# SCH_GPS-rx_2026-03-24.net
KiCad netlist of a schematic drawn in EasyEDA
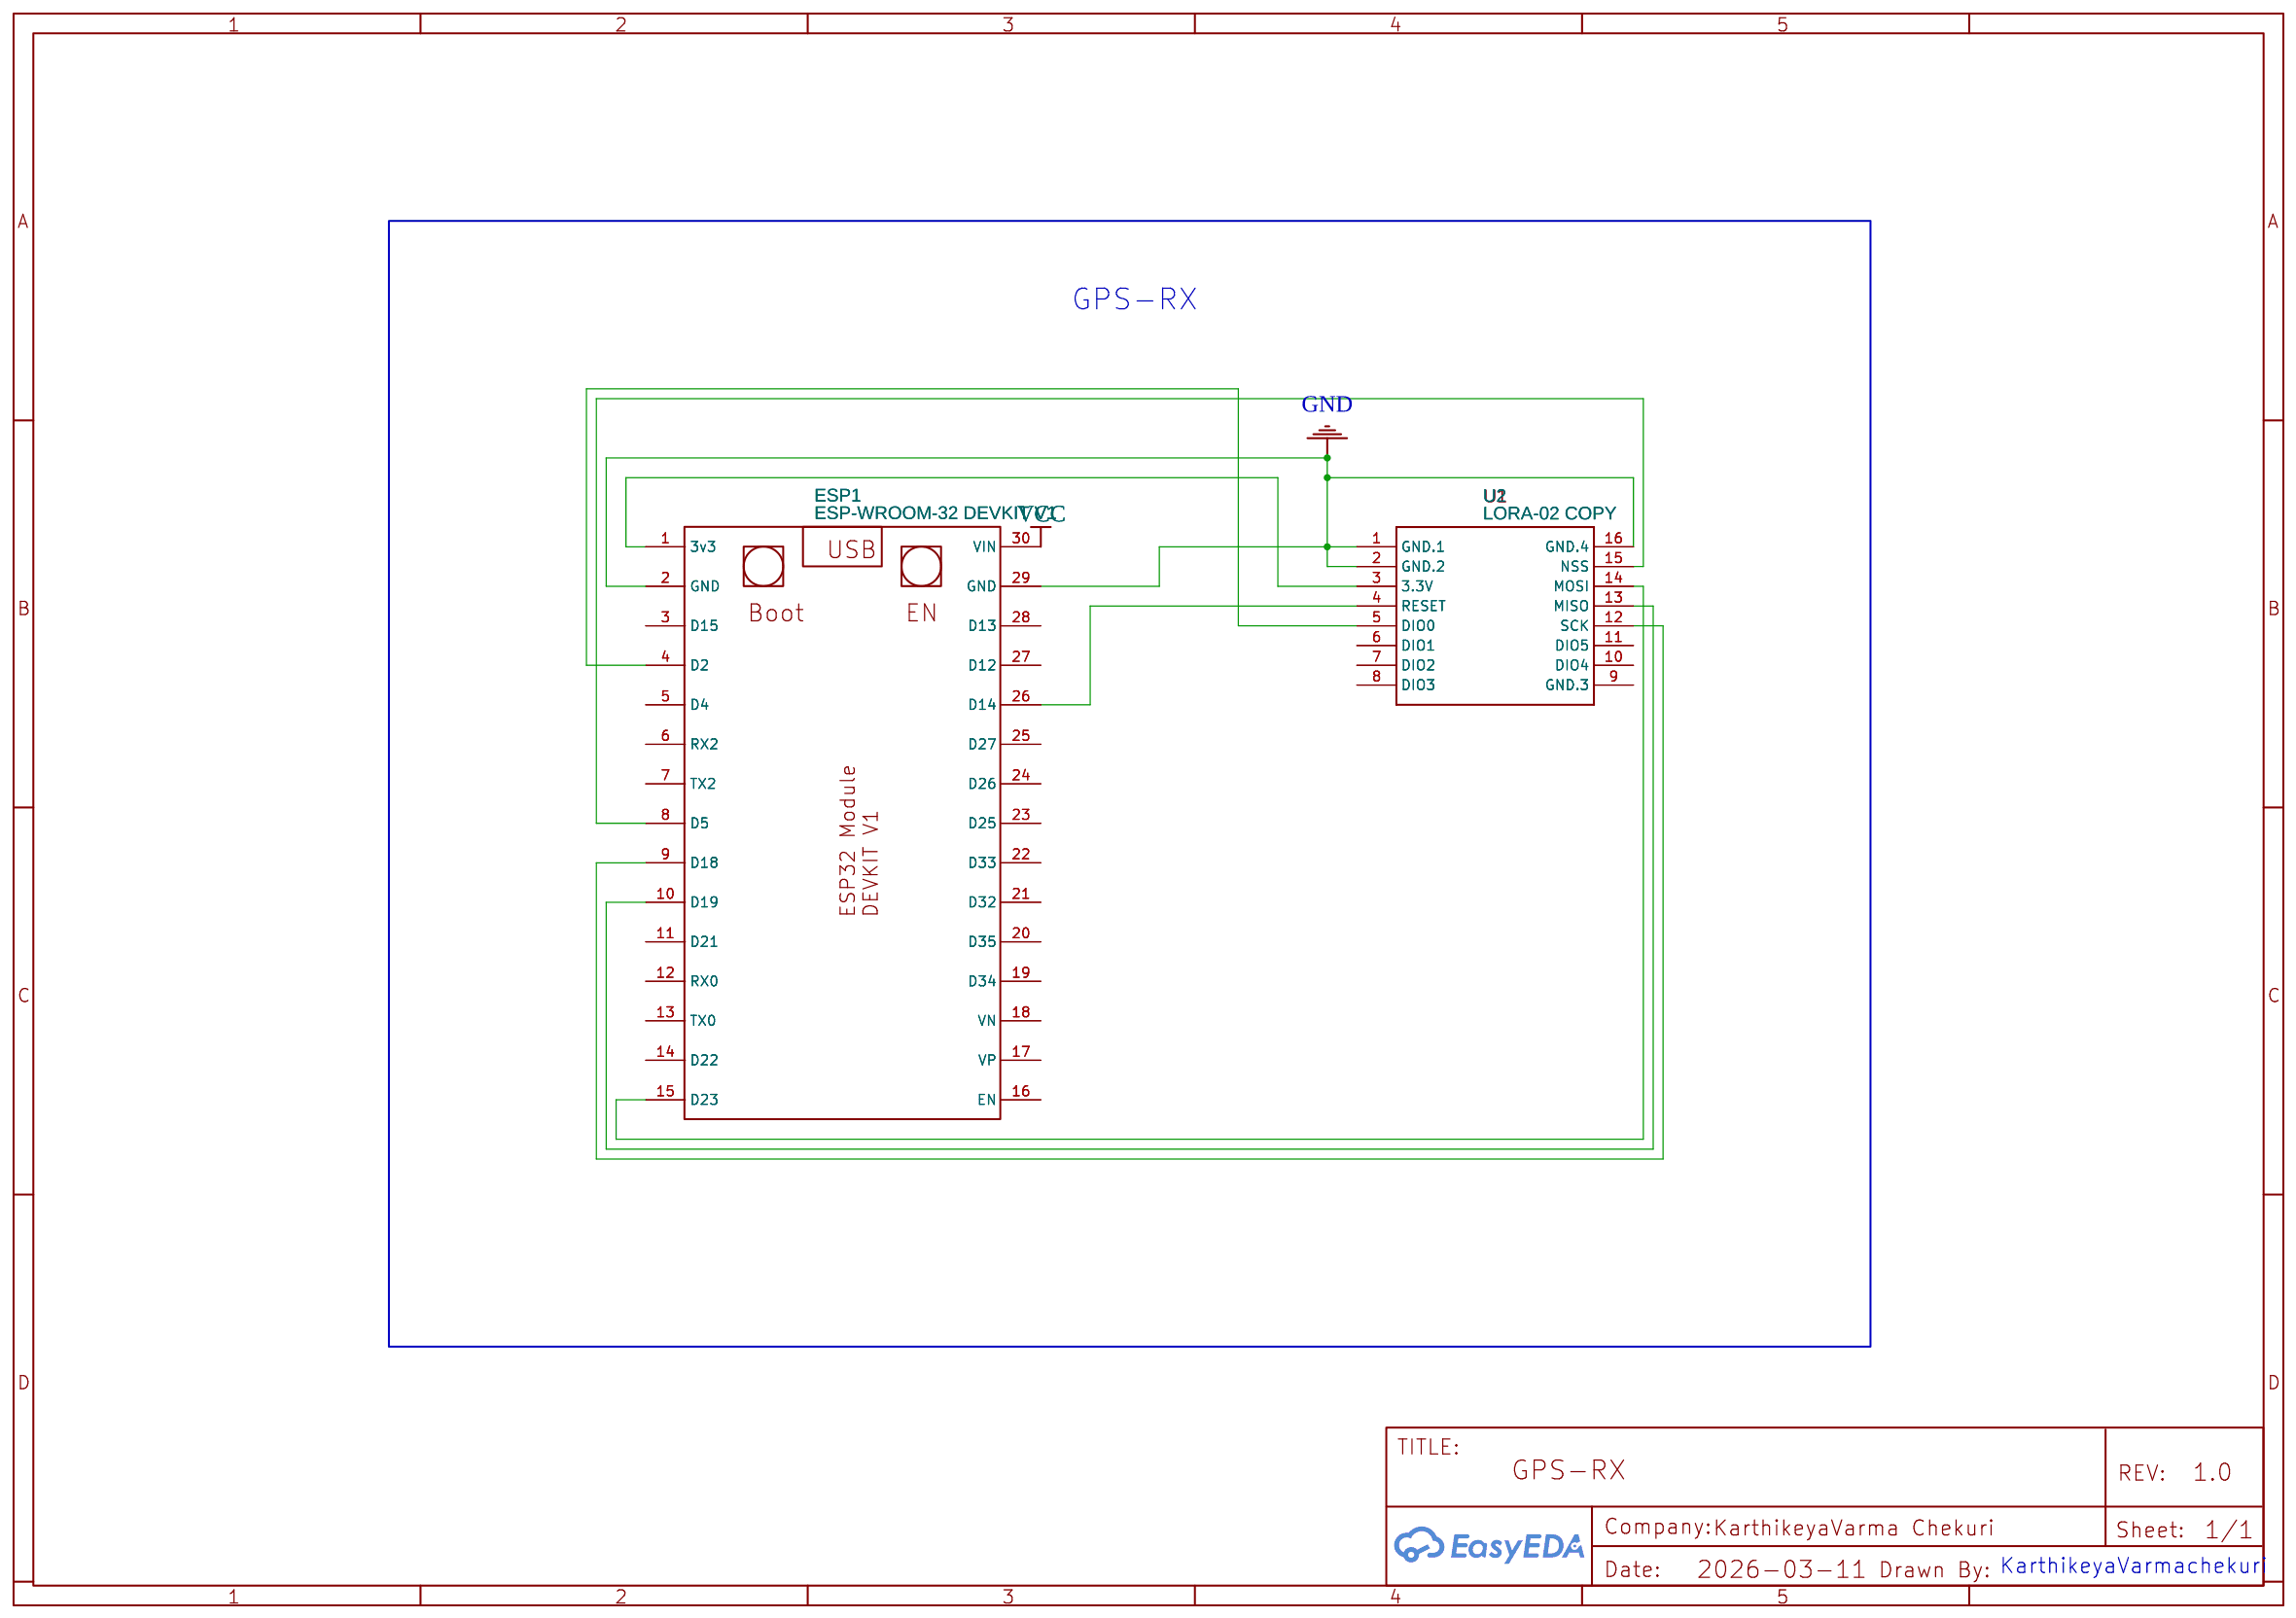
[diagram p0: schematic sheet]

(export (version "E")
  (design (tool "Eeschema 10.0.6"))
  (components
    (comp (ref "ESP1") (value "ESP-WROOM-32 DEVKIT V1") (libsource (lib "") (part "ESP-WROOM-32 DEVKIT V1")))
    (comp (ref "U2") (value "LORA-02 COPY") (libsource (lib "") (part "LORA-02 COPY")))
  )
  (nets
    (net (code "1") (name "GND") (class "Default")
      (node (ref "ESP1") (pin "2") (pinfunction "GND_2") (pintype "unspecified"))
      (node (ref "ESP1") (pin "29") (pinfunction "GND_29") (pintype "unspecified"))
      (node (ref "U2") (pin "1") (pinfunction "GND.1_1") (pintype "passive"))
      (node (ref "U2") (pin "16") (pinfunction "GND.4_16") (pintype "passive"))
      (node (ref "U2") (pin "2") (pinfunction "GND.2_2") (pintype "passive"))
    )
    (net (code "2") (name "Net-(ESP1-3v3)") (class "Default")
      (node (ref "ESP1") (pin "1") (pinfunction "3v3_1") (pintype "unspecified"))
      (node (ref "U2") (pin "3") (pinfunction "3.3V_3") (pintype "passive"))
    )
    (net (code "3") (name "Net-(ESP1-D2)") (class "Default")
      (node (ref "ESP1") (pin "4") (pinfunction "D2_4") (pintype "unspecified"))
      (node (ref "U2") (pin "5") (pinfunction "DIO0_5") (pintype "unspecified"))
    )
    (net (code "4") (name "Net-(ESP1-D5)") (class "Default")
      (node (ref "ESP1") (pin "8") (pinfunction "D5_8") (pintype "unspecified"))
      (node (ref "U2") (pin "15") (pinfunction "NSS_15") (pintype "unspecified"))
    )
    (net (code "5") (name "Net-(ESP1-D14)") (class "Default")
      (node (ref "ESP1") (pin "26") (pinfunction "D14_26") (pintype "unspecified"))
      (node (ref "U2") (pin "4") (pinfunction "RESET_4") (pintype "unspecified"))
    )
    (net (code "6") (name "Net-(ESP1-D18)") (class "Default")
      (node (ref "ESP1") (pin "9") (pinfunction "D18_9") (pintype "unspecified"))
      (node (ref "U2") (pin "12") (pinfunction "SCK_12") (pintype "unspecified"))
    )
    (net (code "7") (name "Net-(ESP1-D19)") (class "Default")
      (node (ref "ESP1") (pin "10") (pinfunction "D19_10") (pintype "unspecified"))
      (node (ref "U2") (pin "13") (pinfunction "MISO_13") (pintype "unspecified"))
    )
    (net (code "8") (name "Net-(ESP1-D23)") (class "Default")
      (node (ref "ESP1") (pin "15") (pinfunction "D23_15") (pintype "unspecified"))
      (node (ref "U2") (pin "14") (pinfunction "MOSI_14") (pintype "unspecified"))
    )
    (net (code "9") (name "VCC") (class "Default")
      (node (ref "ESP1") (pin "30") (pinfunction "VIN_30") (pintype "unspecified"))
    )
    (net (code "10") (name "unconnected-(ESP1-D4-Pad5)") (class "Default")
      (node (ref "ESP1") (pin "5") (pinfunction "D4_5") (pintype "unspecified"))
    )
    (net (code "11") (name "unconnected-(ESP1-D12-Pad27)") (class "Default")
      (node (ref "ESP1") (pin "27") (pinfunction "D12_27") (pintype "unspecified"))
    )
    (net (code "12") (name "unconnected-(ESP1-D13-Pad28)") (class "Default")
      (node (ref "ESP1") (pin "28") (pinfunction "D13_28") (pintype "unspecified"))
    )
    (net (code "13") (name "unconnected-(ESP1-D15-Pad3)") (class "Default")
      (node (ref "ESP1") (pin "3") (pinfunction "D15_3") (pintype "unspecified"))
    )
    (net (code "14") (name "unconnected-(ESP1-D21-Pad11)") (class "Default")
      (node (ref "ESP1") (pin "11") (pinfunction "D21_11") (pintype "unspecified"))
    )
    (net (code "15") (name "unconnected-(ESP1-D22-Pad14)") (class "Default")
      (node (ref "ESP1") (pin "14") (pinfunction "D22_14") (pintype "unspecified"))
    )
    (net (code "16") (name "unconnected-(ESP1-D25-Pad23)") (class "Default")
      (node (ref "ESP1") (pin "23") (pinfunction "D25_23") (pintype "unspecified"))
    )
    (net (code "17") (name "unconnected-(ESP1-D26-Pad24)") (class "Default")
      (node (ref "ESP1") (pin "24") (pinfunction "D26_24") (pintype "unspecified"))
    )
    (net (code "18") (name "unconnected-(ESP1-D27-Pad25)") (class "Default")
      (node (ref "ESP1") (pin "25") (pinfunction "D27_25") (pintype "unspecified"))
    )
    (net (code "19") (name "unconnected-(ESP1-D32-Pad21)") (class "Default")
      (node (ref "ESP1") (pin "21") (pinfunction "D32_21") (pintype "unspecified"))
    )
    (net (code "20") (name "unconnected-(ESP1-D33-Pad22)") (class "Default")
      (node (ref "ESP1") (pin "22") (pinfunction "D33_22") (pintype "unspecified"))
    )
    (net (code "21") (name "unconnected-(ESP1-D34-Pad19)") (class "Default")
      (node (ref "ESP1") (pin "19") (pinfunction "D34_19") (pintype "unspecified"))
    )
    (net (code "22") (name "unconnected-(ESP1-D35-Pad20)") (class "Default")
      (node (ref "ESP1") (pin "20") (pinfunction "D35_20") (pintype "unspecified"))
    )
    (net (code "23") (name "unconnected-(ESP1-EN-Pad16)") (class "Default")
      (node (ref "ESP1") (pin "16") (pinfunction "EN_16") (pintype "unspecified"))
    )
    (net (code "24") (name "unconnected-(ESP1-RX0-Pad12)") (class "Default")
      (node (ref "ESP1") (pin "12") (pinfunction "RX0_12") (pintype "unspecified"))
    )
    (net (code "25") (name "unconnected-(ESP1-RX2-Pad6)") (class "Default")
      (node (ref "ESP1") (pin "6") (pinfunction "RX2_6") (pintype "unspecified"))
    )
    (net (code "26") (name "unconnected-(ESP1-TX0-Pad13)") (class "Default")
      (node (ref "ESP1") (pin "13") (pinfunction "TX0_13") (pintype "unspecified"))
    )
    (net (code "27") (name "unconnected-(ESP1-TX2-Pad7)") (class "Default")
      (node (ref "ESP1") (pin "7") (pinfunction "TX2_7") (pintype "unspecified"))
    )
    (net (code "28") (name "unconnected-(ESP1-VN-Pad18)") (class "Default")
      (node (ref "ESP1") (pin "18") (pinfunction "VN_18") (pintype "unspecified"))
    )
    (net (code "29") (name "unconnected-(ESP1-VP-Pad17)") (class "Default")
      (node (ref "ESP1") (pin "17") (pinfunction "VP_17") (pintype "unspecified"))
    )
    (net (code "30") (name "unconnected-(U2-DIO1-Pad6)") (class "Default")
      (node (ref "U2") (pin "6") (pinfunction "DIO1_6") (pintype "unspecified"))
    )
    (net (code "31") (name "unconnected-(U2-DIO2-Pad7)") (class "Default")
      (node (ref "U2") (pin "7") (pinfunction "DIO2_7") (pintype "unspecified"))
    )
    (net (code "32") (name "unconnected-(U2-DIO3-Pad8)") (class "Default")
      (node (ref "U2") (pin "8") (pinfunction "DIO3_8") (pintype "unspecified"))
    )
    (net (code "33") (name "unconnected-(U2-DIO4-Pad10)") (class "Default")
      (node (ref "U2") (pin "10") (pinfunction "DIO4_10") (pintype "unspecified"))
    )
    (net (code "34") (name "unconnected-(U2-DIO5-Pad11)") (class "Default")
      (node (ref "U2") (pin "11") (pinfunction "DIO5_11") (pintype "unspecified"))
    )
    (net (code "35") (name "unconnected-(U2-GND.3-Pad9)") (class "Default")
      (node (ref "U2") (pin "9") (pinfunction "GND.3_9") (pintype "passive"))
    )
  )
)
